# MA_board_2.net
KiCad netlist of a schematic drawn in EAGLE
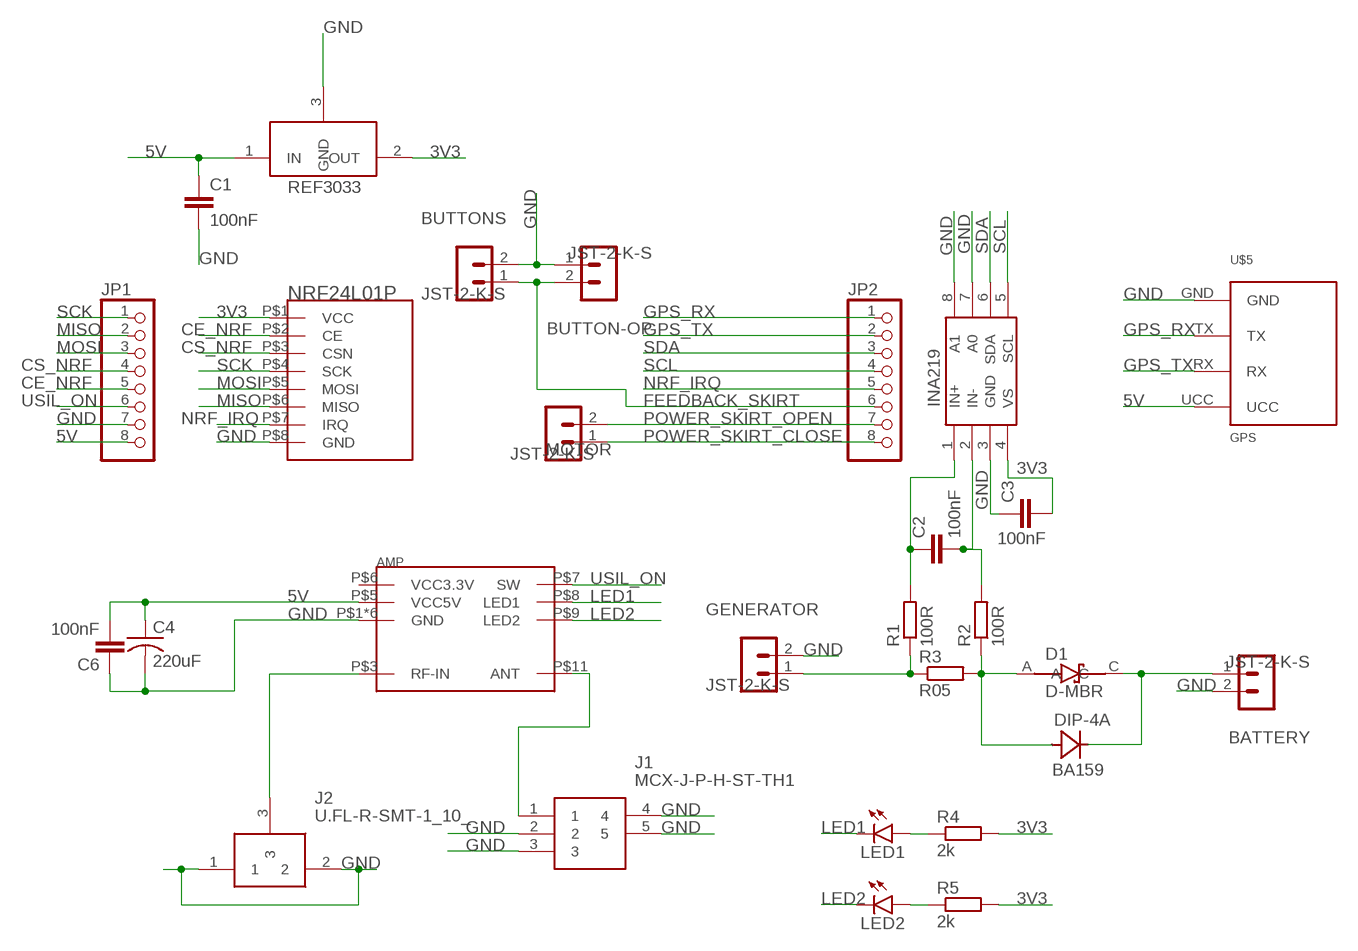
[diagram p0: schematic, sheet 1]

(export (version "E")
  (design (tool "Eeschema 10.0.6"))
  (components
    (comp (ref "AMP")
      (value "XQ-02A")
      (footprint "eagle-import:XQ-02A")
      (libsource (lib "eagle-import") (part "XQ-02A"))
    )
    (comp (ref "BATTERY")
      (value "JST-2-K-S")
      (footprint "eagle-import:B2B-PH-K-S")
      (libsource (lib "eagle-import") (part "JST-2-K-S"))
    )
    (comp (ref "BUTTON-OP")
      (value "JST-2-K-S")
      (footprint "eagle-import:B2B-PH-K-S")
      (libsource (lib "eagle-import") (part "JST-2-K-S"))
    )
    (comp (ref "BUTTONS")
      (value "JST-2-K-S")
      (footprint "eagle-import:B2B-PH-K-S")
      (libsource (lib "eagle-import") (part "JST-2-K-S"))
    )
    (comp (ref "C1")
      (value "100nF")
      (footprint "eagle-import:C0603")
      (libsource (lib "eagle-import") (part "C-EUC0603"))
    )
    (comp (ref "C2")
      (value "100nF")
      (footprint "eagle-import:C0603")
      (libsource (lib "eagle-import") (part "C-EUC0603"))
    )
    (comp (ref "C3")
      (value "100nF")
      (footprint "eagle-import:C0603")
      (libsource (lib "eagle-import") (part "C-EUC0603"))
    )
    (comp (ref "C4")
      (value "220uF")
      (footprint "eagle-import:ECAP220-CMD")
      (libsource (lib "eagle-import") (part "ECAPECAP220"))
    )
    (comp (ref "C6")
      (value "100nF")
      (footprint "eagle-import:C0603")
      (libsource (lib "eagle-import") (part "C-EUC0603"))
    )
    (comp (ref "D1")
      (value "D-MBR")
      (footprint "eagle-import:SOD123")
      (fields (field (name "MF") "ON Semiconductor") (field (name "MP") "MBR0520LT1G"))
      (libsource (lib "eagle-import") (part "DIODE-MBR"))
    )
    (comp (ref "DIP-4A")
      (value "BA159")
      (footprint "eagle-import:BA159")
      (libsource (lib "eagle-import") (part "BA159"))
    )
    (comp (ref "GENERATOR")
      (value "JST-2-K-S")
      (footprint "eagle-import:B2B-PH-K-S")
      (libsource (lib "eagle-import") (part "JST-2-K-S"))
    )
    (comp (ref "INA219")
      (value "INA219AID")
      (footprint "eagle-import:SOT23-8")
      (libsource (lib "eagle-import") (part "INA219AID"))
    )
    (comp (ref "J1")
      (value "MCX-J-P-H-ST-TH1")
      (footprint "eagle-import:MCXJPHSTTH1")
      (fields (field (name "MOUSER_PART_NUMBER") "200-MCXJPHSTTH1"))
      (libsource (lib "eagle-import") (part "MCX-J-P-H-ST-TH1"))
    )
    (comp (ref "J2")
      (value "U.FL-R-SMT-1_10_")
      (footprint "eagle-import:U.FL-R-SMT-1(10)")
      (fields
        (field (name "ARROW_PART_NUMBER") "U.FL-R-SMT-1(10)")
        (field (name "MOUSER_PART_NUMBER") "798-U.FL-R-SMT-110")
      )
      (libsource (lib "eagle-import") (part "U.FL-R-SMT-1_10_"))
    )
    (comp (ref "JP1")
      (value "PINHD-1X8-SHORT-PAD")
      (footprint "eagle-import:1X08")
      (libsource (lib "eagle-import") (part "PINHD-1X8-SHORT-PAD"))
    )
    (comp (ref "JP2")
      (value "PINHD-1X8-SHORT-PAD")
      (footprint "eagle-import:1X08")
      (libsource (lib "eagle-import") (part "PINHD-1X8-SHORT-PAD"))
    )
    (comp (ref "LED1")
      (value "LEDSML0603")
      (footprint "eagle-import:SML0603")
      (libsource (lib "eagle-import") (part "LEDSML0603"))
    )
    (comp (ref "LED2")
      (value "LEDSML0603")
      (footprint "eagle-import:SML0603")
      (libsource (lib "eagle-import") (part "LEDSML0603"))
    )
    (comp (ref "MOTOR")
      (value "JST-2-K-S")
      (footprint "eagle-import:B2B-PH-K-S")
      (libsource (lib "eagle-import") (part "JST-2-K-S"))
    )
    (comp (ref "NRF24L01P")
      (value "NRF24L01_ML01SP4")
      (footprint "eagle-import:NRF24L01_ML01SP4")
      (libsource (lib "eagle-import") (part "NRF24L01_ML01SP4"))
    )
    (comp (ref "R1")
      (value "100R")
      (footprint "eagle-import:R0603")
      (libsource (lib "eagle-import") (part "R-EU_R0603"))
    )
    (comp (ref "R2")
      (value "100R")
      (footprint "eagle-import:R0603")
      (libsource (lib "eagle-import") (part "R-EU_R0603"))
    )
    (comp (ref "R3")
      (value "R05")
      (footprint "eagle-import:R2512")
      (libsource (lib "eagle-import") (part "R-EU_R2512"))
    )
    (comp (ref "R4")
      (value "2k")
      (footprint "eagle-import:R0603")
      (libsource (lib "eagle-import") (part "R-EU_R0603"))
    )
    (comp (ref "R5")
      (value "2k")
      (footprint "eagle-import:R0603")
      (libsource (lib "eagle-import") (part "R-EU_R0603"))
    )
    (comp (ref "REF3033")
      (value "REF3033")
      (footprint "eagle-import:SOT23-3")
      (libsource (lib "eagle-import") (part "REF3033"))
    )
    (comp (ref "U$5")
      (value "GPS")
      (footprint "eagle-import:GPS")
      (libsource (lib "eagle-import") (part "GPS"))
    )
  )
  (nets
    (net (code "1") (name "/3V3") (class "Default")
      (node (ref "C3") (pin "2") (pinfunction "2_2") (pintype "passive"))
      (node (ref "INA219") (pin "4") (pinfunction "VS_4") (pintype "bidirectional"))
      (node (ref "NRF24L01P") (pin "P$1") (pinfunction "VCC_P$1") (pintype "bidirectional"))
      (node (ref "R4") (pin "2") (pinfunction "2_2") (pintype "passive"))
      (node (ref "R5") (pin "2") (pinfunction "2_2") (pintype "passive"))
      (node (ref "REF3033") (pin "2") (pinfunction "OUT_2") (pintype "output"))
    )
    (net (code "2") (name "/5V") (class "Default")
      (node (ref "AMP") (pin "P$5") (pinfunction "VCC5V_P$5") (pintype "bidirectional"))
      (node (ref "C1") (pin "1") (pinfunction "1_1") (pintype "passive"))
      (node (ref "C4") (pin "P$1") (pinfunction "1_P$1") (pintype "passive"))
      (node (ref "C6") (pin "2") (pinfunction "2_2") (pintype "passive"))
      (node (ref "JP1") (pin "8") (pinfunction "8_8") (pintype "passive"))
      (node (ref "REF3033") (pin "1") (pinfunction "IN_1") (pintype "input"))
      (node (ref "U$5") (pin "UCC") (pinfunction "UCC_UCC") (pintype "bidirectional"))
    )
    (net (code "3") (name "/CE_NRF") (class "Default")
      (node (ref "JP1") (pin "5") (pinfunction "5_5") (pintype "passive"))
      (node (ref "NRF24L01P") (pin "P$2") (pinfunction "CE_P$2") (pintype "bidirectional"))
    )
    (net (code "4") (name "/CS_NRF") (class "Default")
      (node (ref "JP1") (pin "4") (pinfunction "4_4") (pintype "passive"))
      (node (ref "NRF24L01P") (pin "P$3") (pinfunction "CSN_P$3") (pintype "bidirectional"))
    )
    (net (code "5") (name "/FEEDBACK_SKIRT") (class "Default")
      (node (ref "BUTTON-OP") (pin "2") (pinfunction "2_2") (pintype "passive"))
      (node (ref "BUTTONS") (pin "1") (pinfunction "1_1") (pintype "passive"))
      (node (ref "JP2") (pin "6") (pinfunction "6_6") (pintype "passive"))
    )
    (net (code "6") (name "/GND") (class "Default")
      (node (ref "AMP") (pin "P$1") (pinfunction "GND_P$1") (pintype "bidirectional"))
      (node (ref "AMP") (pin "P$10") (pinfunction "GND_P$10") (pintype "bidirectional"))
      (node (ref "AMP") (pin "P$12") (pinfunction "GND_P$12") (pintype "bidirectional"))
      (node (ref "AMP") (pin "P$13") (pinfunction "GND_P$13") (pintype "bidirectional"))
      (node (ref "AMP") (pin "P$2") (pinfunction "GND_P$2") (pintype "bidirectional"))
      (node (ref "AMP") (pin "P$4") (pinfunction "GND_P$4") (pintype "bidirectional"))
      (node (ref "BATTERY") (pin "2") (pinfunction "2_2") (pintype "passive"))
      (node (ref "BUTTON-OP") (pin "1") (pinfunction "1_1") (pintype "passive"))
      (node (ref "BUTTONS") (pin "2") (pinfunction "2_2") (pintype "passive"))
      (node (ref "C1") (pin "2") (pinfunction "2_2") (pintype "passive"))
      (node (ref "C3") (pin "1") (pinfunction "1_1") (pintype "passive"))
      (node (ref "C4") (pin "P$2") (pinfunction "2_P$2") (pintype "passive"))
      (node (ref "C6") (pin "1") (pinfunction "1_1") (pintype "passive"))
      (node (ref "GENERATOR") (pin "2") (pinfunction "2_2") (pintype "passive"))
      (node (ref "INA219") (pin "3") (pinfunction "GND_3") (pintype "bidirectional"))
      (node (ref "INA219") (pin "7") (pinfunction "A0_7") (pintype "bidirectional"))
      (node (ref "INA219") (pin "8") (pinfunction "A1_8") (pintype "bidirectional"))
      (node (ref "J1") (pin "2") (pinfunction "2_2") (pintype "bidirectional"))
      (node (ref "J1") (pin "3") (pinfunction "3_3") (pintype "bidirectional"))
      (node (ref "J1") (pin "4") (pinfunction "4_4") (pintype "bidirectional"))
      (node (ref "J1") (pin "5") (pinfunction "5_5") (pintype "bidirectional"))
      (node (ref "J2") (pin "1") (pinfunction "1_1") (pintype "bidirectional"))
      (node (ref "J2") (pin "2") (pinfunction "2_2") (pintype "bidirectional"))
      (node (ref "JP1") (pin "7") (pinfunction "7_7") (pintype "passive"))
      (node (ref "NRF24L01P") (pin "P$8") (pinfunction "GND_P$8") (pintype "bidirectional"))
      (node (ref "REF3033") (pin "3") (pinfunction "GND_3") (pintype "power_in"))
      (node (ref "U$5") (pin "GND") (pinfunction "GND_GND") (pintype "bidirectional"))
    )
    (net (code "7") (name "/GPS_RX") (class "Default")
      (node (ref "JP2") (pin "1") (pinfunction "1_1") (pintype "passive"))
      (node (ref "U$5") (pin "TX") (pinfunction "TX_TX") (pintype "bidirectional"))
    )
    (net (code "8") (name "/GPS_TX") (class "Default")
      (node (ref "JP2") (pin "2") (pinfunction "2_2") (pintype "passive"))
      (node (ref "U$5") (pin "RX") (pinfunction "RX_RX") (pintype "bidirectional"))
    )
    (net (code "9") (name "/LED1") (class "Default")
      (node (ref "AMP") (pin "P$8") (pinfunction "LED1_P$8") (pintype "bidirectional"))
      (node (ref "LED1") (pin "C") (pinfunction "C_C") (pintype "passive"))
    )
    (net (code "10") (name "/LED2") (class "Default")
      (node (ref "AMP") (pin "P$9") (pinfunction "LED2_P$9") (pintype "bidirectional"))
      (node (ref "LED2") (pin "C") (pinfunction "C_C") (pintype "passive"))
    )
    (net (code "11") (name "/MISO") (class "Default")
      (node (ref "JP1") (pin "2") (pinfunction "2_2") (pintype "passive"))
      (node (ref "NRF24L01P") (pin "P$6") (pinfunction "MISO_P$6") (pintype "bidirectional"))
    )
    (net (code "12") (name "/MOSI") (class "Default")
      (node (ref "JP1") (pin "3") (pinfunction "3_3") (pintype "passive"))
      (node (ref "NRF24L01P") (pin "P$5") (pinfunction "MOSI_P$5") (pintype "bidirectional"))
    )
    (net (code "13") (name "/NRF_IRQ") (class "Default")
      (node (ref "JP2") (pin "5") (pinfunction "5_5") (pintype "passive"))
      (node (ref "NRF24L01P") (pin "P$7") (pinfunction "IRQ_P$7") (pintype "bidirectional"))
    )
    (net (code "14") (name "/POWER_SKIRT_CLOSE") (class "Default")
      (node (ref "JP2") (pin "8") (pinfunction "8_8") (pintype "passive"))
      (node (ref "MOTOR") (pin "1") (pinfunction "1_1") (pintype "passive"))
    )
    (net (code "15") (name "/POWER_SKIRT_OPEN") (class "Default")
      (node (ref "JP2") (pin "7") (pinfunction "7_7") (pintype "passive"))
      (node (ref "MOTOR") (pin "2") (pinfunction "2_2") (pintype "passive"))
    )
    (net (code "16") (name "/SCK") (class "Default")
      (node (ref "JP1") (pin "1") (pinfunction "1_1") (pintype "passive"))
      (node (ref "NRF24L01P") (pin "P$4") (pinfunction "SCK_P$4") (pintype "bidirectional"))
    )
    (net (code "17") (name "/SCL") (class "Default")
      (node (ref "INA219") (pin "5") (pinfunction "SCL_5") (pintype "bidirectional"))
      (node (ref "JP2") (pin "4") (pinfunction "4_4") (pintype "passive"))
    )
    (net (code "18") (name "/SDA") (class "Default")
      (node (ref "INA219") (pin "6") (pinfunction "SDA_6") (pintype "bidirectional"))
      (node (ref "JP2") (pin "3") (pinfunction "3_3") (pintype "passive"))
    )
    (net (code "19") (name "/USIL_ON") (class "Default")
      (node (ref "AMP") (pin "P$7") (pinfunction "SW_P$7") (pintype "bidirectional"))
      (node (ref "JP1") (pin "6") (pinfunction "6_6") (pintype "passive"))
    )
    (net (code "20") (name "Net-(AMP-ANT)") (class "Default")
      (node (ref "AMP") (pin "P$11") (pinfunction "ANT_P$11") (pintype "bidirectional"))
      (node (ref "J1") (pin "1") (pinfunction "1_1") (pintype "bidirectional"))
    )
    (net (code "21") (name "Net-(AMP-RF-IN)") (class "Default")
      (node (ref "AMP") (pin "P$3") (pinfunction "RF-IN_P$3") (pintype "bidirectional"))
      (node (ref "J2") (pin "3") (pinfunction "3_3") (pintype "bidirectional"))
    )
    (net (code "22") (name "Net-(DIP-4A-A)") (class "Default")
      (node (ref "D1") (pin "A") (pinfunction "A_A") (pintype "passive"))
      (node (ref "DIP-4A") (pin "P$1") (pinfunction "A_P$1") (pintype "passive"))
      (node (ref "R2") (pin "1") (pinfunction "1_1") (pintype "passive"))
      (node (ref "R3") (pin "2") (pinfunction "2_2") (pintype "passive"))
    )
    (net (code "23") (name "Net-(DIP-4A-C)") (class "Default")
      (node (ref "BATTERY") (pin "1") (pinfunction "1_1") (pintype "passive"))
      (node (ref "D1") (pin "C") (pinfunction "C_C") (pintype "passive"))
      (node (ref "DIP-4A") (pin "P$2") (pinfunction "C_P$2") (pintype "passive"))
    )
    (net (code "24") (name "Net-(GENERATOR-Pad1)") (class "Default")
      (node (ref "GENERATOR") (pin "1") (pinfunction "1_1") (pintype "passive"))
      (node (ref "R1") (pin "1") (pinfunction "1_1") (pintype "passive"))
      (node (ref "R3") (pin "1") (pinfunction "1_1") (pintype "passive"))
    )
    (net (code "25") (name "Net-(INA219-IN+)") (class "Default")
      (node (ref "C2") (pin "1") (pinfunction "1_1") (pintype "passive"))
      (node (ref "INA219") (pin "1") (pinfunction "IN+_1") (pintype "bidirectional"))
      (node (ref "R1") (pin "2") (pinfunction "2_2") (pintype "passive"))
    )
    (net (code "26") (name "Net-(INA219-IN-)") (class "Default")
      (node (ref "C2") (pin "2") (pinfunction "2_2") (pintype "passive"))
      (node (ref "INA219") (pin "2") (pinfunction "IN-_2") (pintype "bidirectional"))
      (node (ref "R2") (pin "2") (pinfunction "2_2") (pintype "passive"))
    )
    (net (code "27") (name "Net-(LED1-PadA)") (class "Default")
      (node (ref "LED1") (pin "A") (pinfunction "A_A") (pintype "passive"))
      (node (ref "R4") (pin "1") (pinfunction "1_1") (pintype "passive"))
    )
    (net (code "28") (name "Net-(LED2-PadA)") (class "Default")
      (node (ref "LED2") (pin "A") (pinfunction "A_A") (pintype "passive"))
      (node (ref "R5") (pin "1") (pinfunction "1_1") (pintype "passive"))
    )
    (net (code "29") (name "unconnected-(AMP-VCC3.3V-PadP$6)") (class "Default")
      (node (ref "AMP") (pin "P$6") (pinfunction "VCC3.3V_P$6") (pintype "bidirectional"))
    )
  )
)
